# Adaptor.net
KiCad netlist of a schematic drawn in Altium Designer
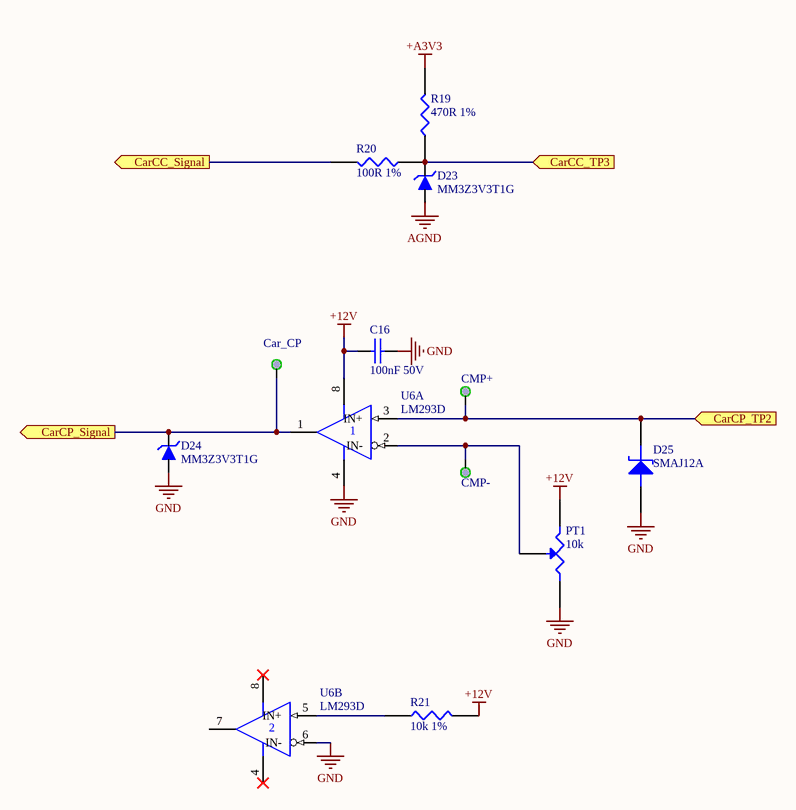
[diagram p0: Adaptor.SchDoc]

(export (version "E")
  (design (tool "Eeschema 10.0.6"))
  (components
    (comp (ref "C16")
      (value "100nF 50V")
      (footprint "Chip_Capacitor_N:CAPC2012N")
      (description "Capacitor")
      (libsource (lib "*") (part "CAP"))
    )
    (comp (ref "Car_CP")
      (value "IR PULSE")
      (footprint "UserPcbLib:TP1.4/1.0")
      (libsource (lib "UserSchlib") (part "TP1.4/1.0"))
    )
    (comp (ref "CMP+")
      (value "CMP+")
      (footprint "UserPcbLib:TP1.4/1.0")
      (libsource (lib "UserSchlib") (part "TP1.4/1.0"))
    )
    (comp (ref "CMP-")
      (value "CMP-")
      (footprint "UserPcbLib:TP1.4/1.0")
      (libsource (lib "UserSchlib") (part "TP1.4/1.0"))
    )
    (comp (ref "D23")
      (value "MM3Z3V3T1G")
      (footprint "Small Outline Diode - 2 Gullwing Leads:SOD-323")
      (description "Zener diode")
      (fields (field (name "MANUFACTURER") "ON"))
      (libsource (lib "UserSchlib") (part "Zener Diode"))
    )
    (comp (ref "D24")
      (value "MM3Z3V3T1G")
      (footprint "Small Outline Diode - 2 Gullwing Leads:SOD-323")
      (description "Zener diode")
      (fields (field (name "MANUFACTURER") "ON"))
      (libsource (lib "UserSchlib") (part "Zener Diode"))
    )
    (comp (ref "D25")
      (value "SMAJ12A")
      (footprint "Small Outline Diode - 2 C-Bend Leads:DSO-C2/G1.6")
      (description "Zener Diode")
      (fields (field (name "MANUFACTURER") "Littlefuse"))
      (libsource (lib "*") (part "ZENER2"))
    )
    (comp (ref "PT1")
      (value "10k")
      (footprint "UserPcbLib:VR-3362P")
      (description "电位器")
      (libsource (lib "*") (part "POT1"))
    )
    (comp (ref "R19")
      (value "470R 1%")
      (footprint "Chip_Resistor_N:RESC2012N")
      (libsource (lib "*") (part "RES1"))
    )
    (comp (ref "R20")
      (value "100R 1%")
      (footprint "Chip_Resistor_N:RESC2012N")
      (libsource (lib "*") (part "RES1"))
    )
    (comp (ref "R21")
      (value "10k 1%")
      (footprint "Chip_Resistor_N:RESC2012N")
      (libsource (lib "*") (part "RES1"))
    )
    (comp (ref "U6")
      (value "LM293D")
      (footprint "ST-Microelectronics Footprints:SO8_M")
      (description "Dual Differential Comparator")
      (fields (field (name "PUBLISHER") "Altium Limited"))
      (libsource (lib "TI Logic Comparator") (part "LM393D"))
    )
  )
  (nets
    (net (code "1") (name "+12V") (class "Default")
      (node (ref "C16") (pin "2") (pinfunction "2_2") (pintype "passive"))
      (node (ref "PT1") (pin "1") (pinfunction "1_1") (pintype "passive"))
      (node (ref "R21") (pin "2") (pinfunction "2_2") (pintype "passive"))
      (node (ref "U6") (pin "8") (pinfunction "VCC_8") (pintype "power_in"))
    )
    (net (code "2") (name "+A3V3") (class "Default")
      (node (ref "R19") (pin "2") (pinfunction "2_2") (pintype "passive"))
    )
    (net (code "3") (name "/CarCC_Signal") (class "Default")
      (node (ref "R20") (pin "2") (pinfunction "2_2") (pintype "passive"))
    )
    (net (code "4") (name "/CarCC_TP3") (class "Default")
      (node (ref "D23") (pin "1") (pinfunction "K_1") (pintype "passive"))
      (node (ref "R19") (pin "1") (pinfunction "1_1") (pintype "passive"))
      (node (ref "R20") (pin "1") (pinfunction "1_1") (pintype "passive"))
    )
    (net (code "5") (name "/CarCP_Signal") (class "Default")
      (node (ref "Car_CP") (pin "1") (pinfunction "1_1") (pintype "passive"))
      (node (ref "D24") (pin "1") (pinfunction "K_1") (pintype "passive"))
      (node (ref "U6") (pin "1") (pinfunction "OUT_1") (pintype "open_collector"))
    )
    (net (code "6") (name "/CarCP_TP2") (class "Default")
      (node (ref "CMP+") (pin "1") (pinfunction "1_1") (pintype "passive"))
      (node (ref "D25") (pin "2") (pinfunction "K_2") (pintype "passive"))
      (node (ref "U6") (pin "3") (pinfunction "IN+_3") (pintype "input"))
    )
    (net (code "7") (name "AGND") (class "Default")
      (node (ref "D23") (pin "2") (pinfunction "A_2") (pintype "passive"))
    )
    (net (code "8") (name "GND") (class "Default")
      (node (ref "C16") (pin "1") (pinfunction "1_1") (pintype "passive"))
      (node (ref "D24") (pin "2") (pinfunction "A_2") (pintype "passive"))
      (node (ref "D25") (pin "1") (pinfunction "A_1") (pintype "passive"))
      (node (ref "PT1") (pin "3") (pinfunction "3_3") (pintype "passive"))
      (node (ref "U6") (pin "4") (pinfunction "GND_4") (pintype "power_in"))
      (node (ref "U6") (pin "6") (pinfunction "IN-_6") (pintype "input"))
    )
    (net (code "9") (name "Net-(PT1-W)") (class "Default")
      (node (ref "CMP-") (pin "1") (pinfunction "1_1") (pintype "passive"))
      (node (ref "PT1") (pin "2") (pinfunction "W_2") (pintype "passive"))
      (node (ref "U6") (pin "2") (pinfunction "IN-_2") (pintype "input"))
    )
    (net (code "10") (name "Net-(U6B-IN+)") (class "Default")
      (node (ref "R21") (pin "1") (pinfunction "1_1") (pintype "passive"))
      (node (ref "U6") (pin "5") (pinfunction "IN+_5") (pintype "input"))
    )
    (net (code "11") (name "unconnected-(U6B-GND-Pad4)") (class "Default")
      (node (ref "U6") (pin "4") (pinfunction "GND_4") (pintype "power_in+no_connect"))
    )
    (net (code "12") (name "unconnected-(U6B-OUT-Pad7)") (class "Default")
      (node (ref "U6") (pin "7") (pinfunction "OUT_7") (pintype "open_collector"))
    )
    (net (code "13") (name "unconnected-(U6B-VCC-Pad8)") (class "Default")
      (node (ref "U6") (pin "8") (pinfunction "VCC_8") (pintype "power_in+no_connect"))
    )
  )
)
